# 5mmtermCuringCircuit.net
KiCad netlist of a schematic drawn in EAGLE
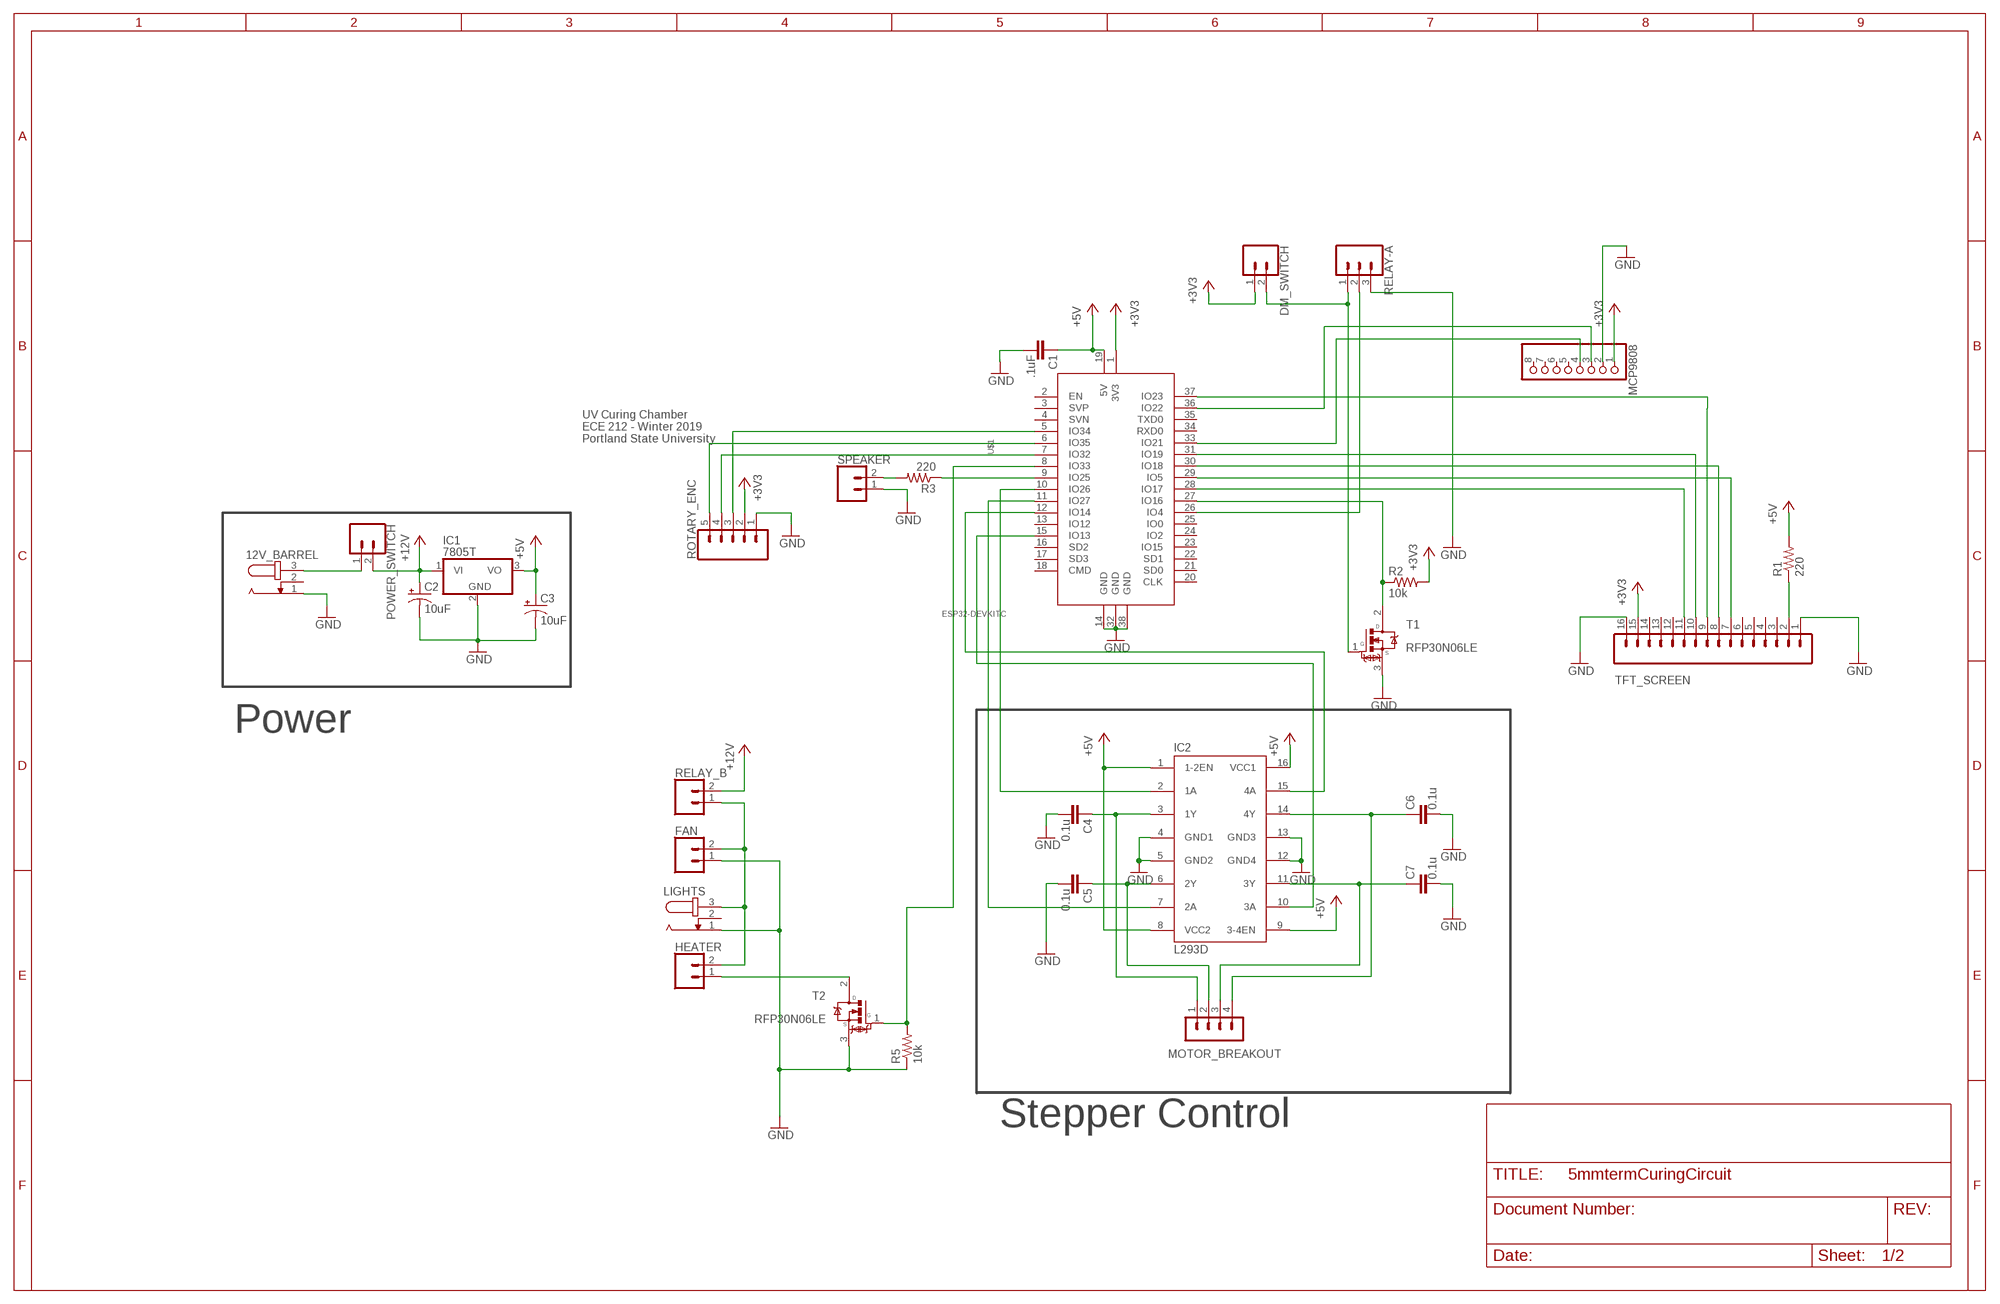
[diagram p0: schematic, sheet 1]

(export (version "E")
  (design (tool "Eeschema 10.0.6"))
  (components
    (comp (ref "12V_BARREL")
      (value "JACK-PLUG0")
      (footprint "eagle-import:SPC4077")
      (libsource (lib "eagle-import") (part "JACK-PLUG0"))
    )
    (comp (ref "C1")
      (value ".1uF")
      (footprint "eagle-import:C075-063X106")
      (libsource (lib "eagle-import") (part "C-EU075-063X106"))
    )
    (comp (ref "C2")
      (value "10uF")
      (footprint "eagle-import:E1,8-4")
      (libsource (lib "eagle-import") (part "CPOL-USE1.8-4"))
    )
    (comp (ref "C3")
      (value "10uF")
      (footprint "eagle-import:E1,8-4")
      (libsource (lib "eagle-import") (part "CPOL-USE1.8-4"))
    )
    (comp (ref "C4")
      (value "0.1u")
      (footprint "eagle-import:C075-063X106")
      (libsource (lib "eagle-import") (part "C-EU075-063X106"))
    )
    (comp (ref "C5")
      (value "0.1u")
      (footprint "eagle-import:C075-063X106")
      (libsource (lib "eagle-import") (part "C-EU075-063X106"))
    )
    (comp (ref "C6")
      (value "0.1u")
      (footprint "eagle-import:C075-063X106")
      (libsource (lib "eagle-import") (part "C-EU075-063X106"))
    )
    (comp (ref "C7")
      (value "0.1u")
      (footprint "eagle-import:C075-063X106")
      (libsource (lib "eagle-import") (part "C-EU075-063X106"))
    )
    (comp (ref "DM_SWITCH")
      (value "CONN_025MM")
      (footprint "eagle-import:SCREWTERMINAL-5MM-2")
      (libsource (lib "eagle-import") (part "CONN_025MM"))
    )
    (comp (ref "FAN")
      (value "CONN_025MM")
      (footprint "eagle-import:SCREWTERMINAL-5MM-2")
      (libsource (lib "eagle-import") (part "CONN_025MM"))
    )
    (comp (ref "HEATER")
      (value "CONN_025MM")
      (footprint "eagle-import:SCREWTERMINAL-5MM-2")
      (libsource (lib "eagle-import") (part "CONN_025MM"))
    )
    (comp (ref "IC1")
      (value "7805T")
      (footprint "eagle-import:TO220H")
      (libsource (lib "eagle-import") (part "78T05"))
    )
    (comp (ref "IC2")
      (value "L293D")
      (footprint "eagle-import:DIL16")
      (libsource (lib "eagle-import") (part "L293D"))
    )
    (comp (ref "LIGHTS")
      (value "JACK-PLUG0")
      (footprint "eagle-import:SPC4077")
      (libsource (lib "eagle-import") (part "JACK-PLUG0"))
    )
    (comp (ref "MCP9808")
      (value "PINHD-1X8BIG")
      (footprint "eagle-import:1X08-BIG")
      (libsource (lib "eagle-import") (part "PINHD-1X8BIG"))
    )
    (comp (ref "MOTOR_BREAKOUT")
      (value "MA04-1")
      (footprint "eagle-import:MA04-1")
      (libsource (lib "eagle-import") (part "MA04-1"))
    )
    (comp (ref "POWER_SWITCH")
      (value "CONN_025MM")
      (footprint "eagle-import:SCREWTERMINAL-5MM-2")
      (libsource (lib "eagle-import") (part "CONN_025MM"))
    )
    (comp (ref "R1")
      (value "220")
      (footprint "eagle-import:0207_10")
      (libsource (lib "eagle-import") (part "R-US_0207/10"))
    )
    (comp (ref "R2")
      (value "10k")
      (footprint "eagle-import:0207_10")
      (libsource (lib "eagle-import") (part "R-US_0207/10"))
    )
    (comp (ref "R3")
      (value "220")
      (footprint "eagle-import:0207_10")
      (libsource (lib "eagle-import") (part "R-US_0207/10"))
    )
    (comp (ref "R5")
      (value "10k")
      (footprint "eagle-import:0207_10")
      (libsource (lib "eagle-import") (part "R-US_0207/10"))
    )
    (comp (ref "RELAY-A")
      (value "CONN_03-SCREW-5MM")
      (footprint "eagle-import:SCREWTERMINAL-5MM-3")
      (libsource (lib "eagle-import") (part "CONN_03-SCREW-5MM"))
    )
    (comp (ref "RELAY_B")
      (value "CONN_025MM")
      (footprint "eagle-import:SCREWTERMINAL-5MM-2")
      (libsource (lib "eagle-import") (part "CONN_025MM"))
    )
    (comp (ref "ROTARY_ENC")
      (value "CONN_05")
      (footprint "eagle-import:1X05")
      (libsource (lib "eagle-import") (part "CONN_05"))
    )
    (comp (ref "SPEAKER")
      (value "CONN_025MM")
      (footprint "eagle-import:SCREWTERMINAL-5MM-2")
      (libsource (lib "eagle-import") (part "CONN_025MM"))
    )
    (comp (ref "T1")
      (value "RFP30N06LE")
      (footprint "eagle-import:TRANS_RFP30N06LE")
      (fields (field (name "MF") "ON Semiconductor"))
      (libsource (lib "eagle-import") (part "RFP30N06LE"))
    )
    (comp (ref "T2")
      (value "RFP30N06LE")
      (footprint "eagle-import:TRANS_RFP30N06LE")
      (fields (field (name "MF") "ON Semiconductor"))
      (libsource (lib "eagle-import") (part "RFP30N06LE"))
    )
    (comp (ref "TFT_SCREEN")
      (value "CONN_16")
      (footprint "eagle-import:1X16")
      (libsource (lib "eagle-import") (part "CONN_16"))
    )
    (comp (ref "U$1")
      (value "ESP32DEVKITC")
      (footprint "eagle-import:ESP32-DEVKITC")
      (libsource (lib "eagle-import") (part "ESP32DEVKITC"))
    )
  )
  (nets
    (net (code "1") (name "+3V3") (class "Default")
      (node (ref "DM_SWITCH") (pin "1") (pinfunction "1_1") (pintype "passive"))
      (node (ref "MCP9808") (pin "1") (pinfunction "1_1") (pintype "passive"))
      (node (ref "R2") (pin "2") (pinfunction "2_2") (pintype "passive"))
      (node (ref "ROTARY_ENC") (pin "2") (pinfunction "2_2") (pintype "passive"))
      (node (ref "TFT_SCREEN") (pin "15") (pinfunction "15_15") (pintype "passive"))
      (node (ref "U$1") (pin "1") (pinfunction "3V3_1") (pintype "bidirectional"))
    )
    (net (code "2") (name "+5V") (class "Default")
      (node (ref "C1") (pin "1") (pinfunction "1_1") (pintype "passive"))
      (node (ref "C3") (pin "+") (pinfunction "+_+") (pintype "passive"))
      (node (ref "IC1") (pin "3") (pinfunction "VO_3") (pintype "passive"))
      (node (ref "IC2") (pin "1") (pinfunction "1-2EN_1") (pintype "input"))
      (node (ref "IC2") (pin "16") (pinfunction "VCC1_16") (pintype "power_in"))
      (node (ref "IC2") (pin "8") (pinfunction "VCC2_8") (pintype "power_in"))
      (node (ref "IC2") (pin "9") (pinfunction "3-4EN_9") (pintype "input"))
      (node (ref "R1") (pin "2") (pinfunction "2_2") (pintype "passive"))
      (node (ref "U$1") (pin "19") (pinfunction "5V_19") (pintype "bidirectional"))
    )
    (net (code "3") (name "GND") (class "Default")
      (node (ref "12V_BARREL") (pin "1") (pinfunction "1_1") (pintype "passive"))
      (node (ref "C1") (pin "2") (pinfunction "2_2") (pintype "passive"))
      (node (ref "C2") (pin "-") (pinfunction "-_-") (pintype "passive"))
      (node (ref "C3") (pin "-") (pinfunction "-_-") (pintype "passive"))
      (node (ref "C4") (pin "2") (pinfunction "2_2") (pintype "passive"))
      (node (ref "C5") (pin "2") (pinfunction "2_2") (pintype "passive"))
      (node (ref "C6") (pin "2") (pinfunction "2_2") (pintype "passive"))
      (node (ref "C7") (pin "2") (pinfunction "2_2") (pintype "passive"))
      (node (ref "FAN") (pin "1") (pinfunction "1_1") (pintype "passive"))
      (node (ref "IC1") (pin "2") (pinfunction "GND_2") (pintype "passive"))
      (node (ref "IC2") (pin "12") (pinfunction "GND4_12") (pintype "power_in"))
      (node (ref "IC2") (pin "13") (pinfunction "GND3_13") (pintype "power_in"))
      (node (ref "IC2") (pin "4") (pinfunction "GND1_4") (pintype "power_in"))
      (node (ref "IC2") (pin "5") (pinfunction "GND2_5") (pintype "power_in"))
      (node (ref "LIGHTS") (pin "1") (pinfunction "1_1") (pintype "passive"))
      (node (ref "MCP9808") (pin "2") (pinfunction "2_2") (pintype "passive"))
      (node (ref "R5") (pin "1") (pinfunction "1_1") (pintype "passive"))
      (node (ref "RELAY-A") (pin "3") (pinfunction "3_3") (pintype "passive"))
      (node (ref "ROTARY_ENC") (pin "1") (pinfunction "1_1") (pintype "passive"))
      (node (ref "SPEAKER") (pin "1") (pinfunction "1_1") (pintype "passive"))
      (node (ref "T1") (pin "3") (pinfunction "S_3") (pintype "power_in"))
      (node (ref "T2") (pin "3") (pinfunction "S_3") (pintype "power_in"))
      (node (ref "TFT_SCREEN") (pin "1") (pinfunction "1_1") (pintype "passive"))
      (node (ref "TFT_SCREEN") (pin "16") (pinfunction "16_16") (pintype "passive"))
      (node (ref "U$1") (pin "14") (pinfunction "GND_14") (pintype "bidirectional"))
      (node (ref "U$1") (pin "32") (pinfunction "GND_32") (pintype "bidirectional"))
      (node (ref "U$1") (pin "38") (pinfunction "GND_38") (pintype "bidirectional"))
    )
    (net (code "4") (name "Net-(12V_BARREL-Pad3)") (class "Default")
      (node (ref "12V_BARREL") (pin "3") (pinfunction "3_3") (pintype "passive"))
      (node (ref "POWER_SWITCH") (pin "1") (pinfunction "1_1") (pintype "passive"))
    )
    (net (code "5") (name "Net-(FAN-Pad2)") (class "Default")
      (node (ref "FAN") (pin "2") (pinfunction "2_2") (pintype "passive"))
      (node (ref "HEATER") (pin "2") (pinfunction "2_2") (pintype "passive"))
      (node (ref "LIGHTS") (pin "3") (pinfunction "3_3") (pintype "passive"))
      (node (ref "RELAY_B") (pin "1") (pinfunction "1_1") (pintype "passive"))
    )
    (net (code "6") (name "Net-(IC2-1A)") (class "Default")
      (node (ref "IC2") (pin "2") (pinfunction "1A_2") (pintype "input"))
      (node (ref "U$1") (pin "10") (pinfunction "IO26_10") (pintype "bidirectional"))
    )
    (net (code "7") (name "Net-(IC2-1Y)") (class "Default")
      (node (ref "C4") (pin "1") (pinfunction "1_1") (pintype "passive"))
      (node (ref "IC2") (pin "3") (pinfunction "1Y_3") (pintype "output"))
      (node (ref "MOTOR_BREAKOUT") (pin "1") (pinfunction "1_1") (pintype "passive"))
    )
    (net (code "8") (name "Net-(IC2-2A)") (class "Default")
      (node (ref "IC2") (pin "7") (pinfunction "2A_7") (pintype "input"))
      (node (ref "U$1") (pin "11") (pinfunction "IO27_11") (pintype "bidirectional"))
    )
    (net (code "9") (name "Net-(IC2-2Y)") (class "Default")
      (node (ref "C5") (pin "1") (pinfunction "1_1") (pintype "passive"))
      (node (ref "IC2") (pin "6") (pinfunction "2Y_6") (pintype "output"))
      (node (ref "MOTOR_BREAKOUT") (pin "2") (pinfunction "2_2") (pintype "passive"))
    )
    (net (code "10") (name "Net-(IC2-3A)") (class "Default")
      (node (ref "IC2") (pin "10") (pinfunction "3A_10") (pintype "input"))
      (node (ref "U$1") (pin "15") (pinfunction "IO13_15") (pintype "bidirectional"))
    )
    (net (code "11") (name "Net-(IC2-3Y)") (class "Default")
      (node (ref "C7") (pin "1") (pinfunction "1_1") (pintype "passive"))
      (node (ref "IC2") (pin "11") (pinfunction "3Y_11") (pintype "output"))
      (node (ref "MOTOR_BREAKOUT") (pin "3") (pinfunction "3_3") (pintype "passive"))
    )
    (net (code "12") (name "Net-(IC2-4A)") (class "Default")
      (node (ref "IC2") (pin "15") (pinfunction "4A_15") (pintype "input"))
      (node (ref "U$1") (pin "12") (pinfunction "IO14_12") (pintype "bidirectional"))
    )
    (net (code "13") (name "Net-(IC2-4Y)") (class "Default")
      (node (ref "C6") (pin "1") (pinfunction "1_1") (pintype "passive"))
      (node (ref "IC2") (pin "14") (pinfunction "4Y_14") (pintype "output"))
      (node (ref "MOTOR_BREAKOUT") (pin "4") (pinfunction "4_4") (pintype "passive"))
    )
    (net (code "14") (name "Net-(R1-Pad1)") (class "Default")
      (node (ref "R1") (pin "1") (pinfunction "1_1") (pintype "passive"))
      (node (ref "TFT_SCREEN") (pin "2") (pinfunction "2_2") (pintype "passive"))
    )
    (net (code "15") (name "Net-(R3-Pad2)") (class "Default")
      (node (ref "R3") (pin "2") (pinfunction "2_2") (pintype "passive"))
      (node (ref "SPEAKER") (pin "2") (pinfunction "2_2") (pintype "passive"))
    )
    (net (code "16") (name "Net-(T1-D)") (class "Default")
      (node (ref "R2") (pin "1") (pinfunction "1_1") (pintype "passive"))
      (node (ref "T1") (pin "2") (pinfunction "D_2") (pintype "power_in"))
      (node (ref "U$1") (pin "27") (pinfunction "IO16_27") (pintype "bidirectional"))
    )
    (net (code "17") (name "Net-(T1-G)") (class "Default")
      (node (ref "DM_SWITCH") (pin "2") (pinfunction "2_2") (pintype "passive"))
      (node (ref "RELAY-A") (pin "1") (pinfunction "1_1") (pintype "passive"))
      (node (ref "T1") (pin "1") (pinfunction "G_1") (pintype "input"))
    )
    (net (code "18") (name "Net-(T2-D)") (class "Default")
      (node (ref "HEATER") (pin "1") (pinfunction "1_1") (pintype "passive"))
      (node (ref "T2") (pin "2") (pinfunction "D_2") (pintype "power_in"))
    )
    (net (code "19") (name "Net-(T2-G)") (class "Default")
      (node (ref "R5") (pin "2") (pinfunction "2_2") (pintype "passive"))
      (node (ref "T2") (pin "1") (pinfunction "G_1") (pintype "input"))
      (node (ref "U$1") (pin "8") (pinfunction "IO33_8") (pintype "bidirectional"))
    )
    (net (code "20") (name "Net-(U$1-IO4)") (class "Default")
      (node (ref "RELAY-A") (pin "2") (pinfunction "2_2") (pintype "passive"))
      (node (ref "U$1") (pin "26") (pinfunction "IO4_26") (pintype "bidirectional"))
    )
    (net (code "21") (name "Net-(U$1-IO5)") (class "Default")
      (node (ref "TFT_SCREEN") (pin "7") (pinfunction "7_7") (pintype "passive"))
      (node (ref "U$1") (pin "29") (pinfunction "IO5_29") (pintype "bidirectional"))
    )
    (net (code "22") (name "Net-(U$1-IO17)") (class "Default")
      (node (ref "TFT_SCREEN") (pin "11") (pinfunction "11_11") (pintype "passive"))
      (node (ref "U$1") (pin "28") (pinfunction "IO17_28") (pintype "bidirectional"))
    )
    (net (code "23") (name "Net-(U$1-IO18)") (class "Default")
      (node (ref "TFT_SCREEN") (pin "8") (pinfunction "8_8") (pintype "passive"))
      (node (ref "U$1") (pin "30") (pinfunction "IO18_30") (pintype "bidirectional"))
    )
    (net (code "24") (name "Net-(U$1-IO19)") (class "Default")
      (node (ref "TFT_SCREEN") (pin "10") (pinfunction "10_10") (pintype "passive"))
      (node (ref "U$1") (pin "31") (pinfunction "IO19_31") (pintype "bidirectional"))
    )
    (net (code "25") (name "Net-(U$1-IO21)") (class "Default")
      (node (ref "MCP9808") (pin "4") (pinfunction "4_4") (pintype "passive"))
      (node (ref "U$1") (pin "33") (pinfunction "IO21_33") (pintype "bidirectional"))
    )
    (net (code "26") (name "Net-(U$1-IO22)") (class "Default")
      (node (ref "MCP9808") (pin "3") (pinfunction "3_3") (pintype "passive"))
      (node (ref "U$1") (pin "36") (pinfunction "IO22_36") (pintype "bidirectional"))
    )
    (net (code "27") (name "Net-(U$1-IO23)") (class "Default")
      (node (ref "TFT_SCREEN") (pin "9") (pinfunction "9_9") (pintype "passive"))
      (node (ref "U$1") (pin "37") (pinfunction "IO23_37") (pintype "bidirectional"))
    )
    (net (code "28") (name "Net-(U$1-IO25)") (class "Default")
      (node (ref "R3") (pin "1") (pinfunction "1_1") (pintype "passive"))
      (node (ref "U$1") (pin "9") (pinfunction "IO25_9") (pintype "bidirectional"))
    )
    (net (code "29") (name "Net-(U$1-IO32)") (class "Default")
      (node (ref "ROTARY_ENC") (pin "4") (pinfunction "4_4") (pintype "passive"))
      (node (ref "U$1") (pin "7") (pinfunction "IO32_7") (pintype "bidirectional"))
    )
    (net (code "30") (name "Net-(U$1-IO34)") (class "Default")
      (node (ref "ROTARY_ENC") (pin "3") (pinfunction "3_3") (pintype "passive"))
      (node (ref "U$1") (pin "5") (pinfunction "IO34_5") (pintype "bidirectional"))
    )
    (net (code "31") (name "Net-(U$1-IO35)") (class "Default")
      (node (ref "ROTARY_ENC") (pin "5") (pinfunction "5_5") (pintype "passive"))
      (node (ref "U$1") (pin "6") (pinfunction "IO35_6") (pintype "bidirectional"))
    )
    (net (code "32") (name "V+") (class "Default")
      (node (ref "C2") (pin "+") (pinfunction "+_+") (pintype "passive"))
      (node (ref "IC1") (pin "1") (pinfunction "VI_1") (pintype "input"))
      (node (ref "POWER_SWITCH") (pin "2") (pinfunction "2_2") (pintype "passive"))
      (node (ref "RELAY_B") (pin "2") (pinfunction "2_2") (pintype "passive"))
    )
    (net (code "33") (name "unconnected-(12V_BARREL-Pad2)") (class "Default")
      (node (ref "12V_BARREL") (pin "2") (pinfunction "2_2") (pintype "passive"))
    )
    (net (code "34") (name "unconnected-(LIGHTS-Pad2)") (class "Default")
      (node (ref "LIGHTS") (pin "2") (pinfunction "2_2") (pintype "passive"))
    )
    (net (code "35") (name "unconnected-(MCP9808-Pad5)") (class "Default")
      (node (ref "MCP9808") (pin "5") (pinfunction "5_5") (pintype "passive"))
    )
    (net (code "36") (name "unconnected-(MCP9808-Pad6)") (class "Default")
      (node (ref "MCP9808") (pin "6") (pinfunction "6_6") (pintype "passive"))
    )
    (net (code "37") (name "unconnected-(MCP9808-Pad7)") (class "Default")
      (node (ref "MCP9808") (pin "7") (pinfunction "7_7") (pintype "passive"))
    )
    (net (code "38") (name "unconnected-(MCP9808-Pad8)") (class "Default")
      (node (ref "MCP9808") (pin "8") (pinfunction "8_8") (pintype "passive"))
    )
    (net (code "39") (name "unconnected-(TFT_SCREEN-Pad3)") (class "Default")
      (node (ref "TFT_SCREEN") (pin "3") (pinfunction "3_3") (pintype "passive"))
    )
    (net (code "40") (name "unconnected-(TFT_SCREEN-Pad4)") (class "Default")
      (node (ref "TFT_SCREEN") (pin "4") (pinfunction "4_4") (pintype "passive"))
    )
    (net (code "41") (name "unconnected-(TFT_SCREEN-Pad5)") (class "Default")
      (node (ref "TFT_SCREEN") (pin "5") (pinfunction "5_5") (pintype "passive"))
    )
    (net (code "42") (name "unconnected-(TFT_SCREEN-Pad6)") (class "Default")
      (node (ref "TFT_SCREEN") (pin "6") (pinfunction "6_6") (pintype "passive"))
    )
    (net (code "43") (name "unconnected-(TFT_SCREEN-Pad12)") (class "Default")
      (node (ref "TFT_SCREEN") (pin "12") (pinfunction "12_12") (pintype "passive"))
    )
    (net (code "44") (name "unconnected-(TFT_SCREEN-Pad13)") (class "Default")
      (node (ref "TFT_SCREEN") (pin "13") (pinfunction "13_13") (pintype "passive"))
    )
    (net (code "45") (name "unconnected-(TFT_SCREEN-Pad14)") (class "Default")
      (node (ref "TFT_SCREEN") (pin "14") (pinfunction "14_14") (pintype "passive"))
    )
    (net (code "46") (name "unconnected-(U$1-CLK-Pad20)") (class "Default")
      (node (ref "U$1") (pin "20") (pinfunction "CLK_20") (pintype "bidirectional"))
    )
    (net (code "47") (name "unconnected-(U$1-CMD-Pad18)") (class "Default")
      (node (ref "U$1") (pin "18") (pinfunction "CMD_18") (pintype "bidirectional"))
    )
    (net (code "48") (name "unconnected-(U$1-EN-Pad2)") (class "Default")
      (node (ref "U$1") (pin "2") (pinfunction "EN_2") (pintype "bidirectional"))
    )
    (net (code "49") (name "unconnected-(U$1-IO0-Pad25)") (class "Default")
      (node (ref "U$1") (pin "25") (pinfunction "IO0_25") (pintype "bidirectional"))
    )
    (net (code "50") (name "unconnected-(U$1-IO2-Pad24)") (class "Default")
      (node (ref "U$1") (pin "24") (pinfunction "IO2_24") (pintype "bidirectional"))
    )
    (net (code "51") (name "unconnected-(U$1-IO12-Pad13)") (class "Default")
      (node (ref "U$1") (pin "13") (pinfunction "IO12_13") (pintype "bidirectional"))
    )
    (net (code "52") (name "unconnected-(U$1-IO15-Pad23)") (class "Default")
      (node (ref "U$1") (pin "23") (pinfunction "IO15_23") (pintype "bidirectional"))
    )
    (net (code "53") (name "unconnected-(U$1-RXD0-Pad34)") (class "Default")
      (node (ref "U$1") (pin "34") (pinfunction "RXD0_34") (pintype "bidirectional"))
    )
    (net (code "54") (name "unconnected-(U$1-SD0-Pad21)") (class "Default")
      (node (ref "U$1") (pin "21") (pinfunction "SD0_21") (pintype "bidirectional"))
    )
    (net (code "55") (name "unconnected-(U$1-SD1-Pad22)") (class "Default")
      (node (ref "U$1") (pin "22") (pinfunction "SD1_22") (pintype "bidirectional"))
    )
    (net (code "56") (name "unconnected-(U$1-SD2-Pad16)") (class "Default")
      (node (ref "U$1") (pin "16") (pinfunction "SD2_16") (pintype "bidirectional"))
    )
    (net (code "57") (name "unconnected-(U$1-SD3-Pad17)") (class "Default")
      (node (ref "U$1") (pin "17") (pinfunction "SD3_17") (pintype "bidirectional"))
    )
    (net (code "58") (name "unconnected-(U$1-SVN-Pad4)") (class "Default")
      (node (ref "U$1") (pin "4") (pinfunction "SVN_4") (pintype "bidirectional"))
    )
    (net (code "59") (name "unconnected-(U$1-SVP-Pad3)") (class "Default")
      (node (ref "U$1") (pin "3") (pinfunction "SVP_3") (pintype "bidirectional"))
    )
    (net (code "60") (name "unconnected-(U$1-TXD0-Pad35)") (class "Default")
      (node (ref "U$1") (pin "35") (pinfunction "TXD0_35") (pintype "bidirectional"))
    )
  )
)
